# AFE_old.net
KiCad netlist of a schematic drawn in Altium Designer
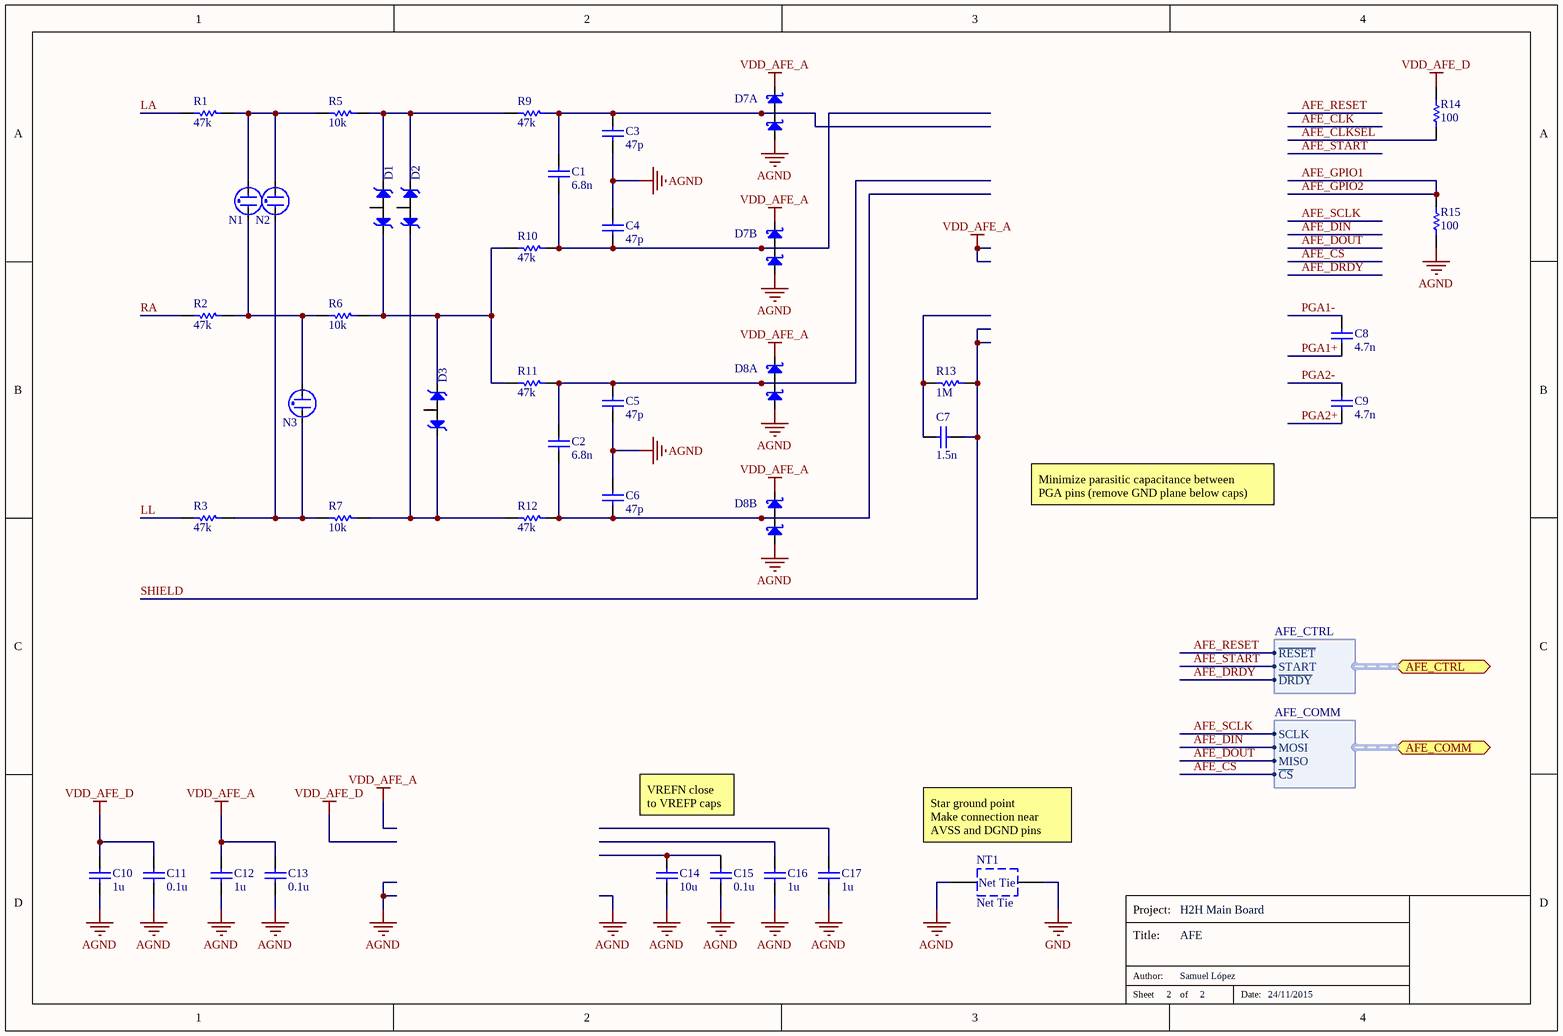
[diagram p0: AFE_old.SchDoc]

(export (version "E")
  (design (tool "Eeschema 10.0.6"))
  (components
    (comp (ref "C1")
      (value "6.8n")
      (footprint "C0603")
      (description "Capacitor")
      (libsource (lib "Common Devices") (part "Capacitor"))
    )
    (comp (ref "C2")
      (value "6.8n")
      (footprint "C0603")
      (description "Capacitor")
      (libsource (lib "Common Devices") (part "Capacitor"))
    )
    (comp (ref "C3")
      (value "47p")
      (footprint "C0603")
      (description "Capacitor")
      (libsource (lib "Common Devices") (part "Capacitor"))
    )
    (comp (ref "C4")
      (value "47p")
      (footprint "C0603")
      (description "Capacitor")
      (libsource (lib "Common Devices") (part "Capacitor"))
    )
    (comp (ref "C5")
      (value "47p")
      (footprint "C0603")
      (description "Capacitor")
      (libsource (lib "Common Devices") (part "Capacitor"))
    )
    (comp (ref "C6")
      (value "47p")
      (footprint "C0603")
      (description "Capacitor")
      (libsource (lib "Common Devices") (part "Capacitor"))
    )
    (comp (ref "C7")
      (value "1.5n")
      (footprint "C0603")
      (description "Capacitor")
      (libsource (lib "Common Devices") (part "Capacitor"))
    )
    (comp (ref "C8")
      (value "4.7n")
      (footprint "C0603")
      (description "Capacitor")
      (libsource (lib "Common Devices") (part "Capacitor"))
    )
    (comp (ref "C9")
      (value "4.7n")
      (footprint "C0603")
      (description "Capacitor")
      (libsource (lib "Common Devices") (part "Capacitor"))
    )
    (comp (ref "C10")
      (value "1u")
      (footprint "C0603")
      (description "Capacitor")
      (libsource (lib "Common Devices") (part "Capacitor"))
    )
    (comp (ref "C11")
      (value "0.1u")
      (footprint "C0603")
      (description "Capacitor")
      (libsource (lib "Common Devices") (part "Capacitor"))
    )
    (comp (ref "C12")
      (value "1u")
      (footprint "C0603")
      (description "Capacitor")
      (libsource (lib "Common Devices") (part "Capacitor"))
    )
    (comp (ref "C13")
      (value "0.1u")
      (footprint "C0603")
      (description "Capacitor")
      (libsource (lib "Common Devices") (part "Capacitor"))
    )
    (comp (ref "C14")
      (value "10u")
      (footprint "C0603")
      (description "Capacitor")
      (libsource (lib "Common Devices") (part "Capacitor"))
    )
    (comp (ref "C15")
      (value "0.1u")
      (footprint "C0603")
      (description "Capacitor")
      (libsource (lib "Common Devices") (part "Capacitor"))
    )
    (comp (ref "C16")
      (value "1u")
      (footprint "C0603")
      (description "Capacitor")
      (libsource (lib "Common Devices") (part "Capacitor"))
    )
    (comp (ref "C17")
      (value "1u")
      (footprint "C0603")
      (description "Capacitor")
      (libsource (lib "Common Devices") (part "Capacitor"))
    )
    (comp (ref "D1")
      (value "PESD5V0X1BT")
      (footprint "SOT23-3")
      (description "TVS Diode - Bidirectional")
      (libsource (lib "Main Board") (part "PESD5V0X1"))
    )
    (comp (ref "D2")
      (value "PESD5V0X1BT")
      (footprint "SOT23-3")
      (description "TVS Diode - Bidirectional")
      (libsource (lib "Main Board") (part "PESD5V0X1"))
    )
    (comp (ref "D3")
      (value "PESD5V0X1BT")
      (footprint "SOT23-3")
      (description "TVS Diode - Bidirectional")
      (libsource (lib "Main Board") (part "PESD5V0X1"))
    )
    (comp (ref "D7")
      (value "BAS70DW-04")
      (footprint "SOT-363")
      (description "Schottky Diode - Array")
      (libsource (lib "Main Board") (part "BAS70DW-04"))
    )
    (comp (ref "D8")
      (value "BAS70DW-04")
      (footprint "SOT-363")
      (description "Schottky Diode - Array")
      (libsource (lib "Main Board") (part "BAS70DW-04"))
    )
    (comp (ref "N1")
      (value "GDT")
      (footprint "1812 GDT")
      (description "GDT - Gas Discharge Tube")
      (libsource (lib "Main Board") (part "2051-09-SM"))
    )
    (comp (ref "N2")
      (value "GDT")
      (footprint "1812 GDT")
      (description "GDT - Gas Discharge Tube")
      (libsource (lib "Main Board") (part "2051-09-SM"))
    )
    (comp (ref "N3")
      (value "GDT")
      (footprint "1812 GDT")
      (description "GDT - Gas Discharge Tube")
      (libsource (lib "Main Board") (part "2051-09-SM"))
    )
    (comp (ref "NT1")
      (value "Net Tie")
      (footprint "Net Tie (AGND-DGND)")
      (description "Net Tie (AGND-DGND)")
      (libsource (lib "Common Devices") (part "Net Tie"))
    )
    (comp (ref "R1")
      (value "47k")
      (footprint "R0603")
      (description "Resistor")
      (libsource (lib "Common Devices") (part "Resistor"))
    )
    (comp (ref "R2")
      (value "47k")
      (footprint "R0603")
      (description "Resistor")
      (libsource (lib "Common Devices") (part "Resistor"))
    )
    (comp (ref "R3")
      (value "47k")
      (footprint "R0603")
      (description "Resistor")
      (libsource (lib "Common Devices") (part "Resistor"))
    )
    (comp (ref "R5")
      (value "10k")
      (footprint "R0603")
      (description "Resistor")
      (libsource (lib "Common Devices") (part "Resistor"))
    )
    (comp (ref "R6")
      (value "10k")
      (footprint "R0603")
      (description "Resistor")
      (libsource (lib "Common Devices") (part "Resistor"))
    )
    (comp (ref "R7")
      (value "10k")
      (footprint "R0603")
      (description "Resistor")
      (libsource (lib "Common Devices") (part "Resistor"))
    )
    (comp (ref "R9")
      (value "47k")
      (footprint "R0603")
      (description "Resistor")
      (libsource (lib "Common Devices") (part "Resistor"))
    )
    (comp (ref "R10")
      (value "47k")
      (footprint "R0603")
      (description "Resistor")
      (libsource (lib "Common Devices") (part "Resistor"))
    )
    (comp (ref "R11")
      (value "47k")
      (footprint "R0603")
      (description "Resistor")
      (libsource (lib "Common Devices") (part "Resistor"))
    )
    (comp (ref "R12")
      (value "47k")
      (footprint "R0603")
      (description "Resistor")
      (libsource (lib "Common Devices") (part "Resistor"))
    )
    (comp (ref "R13")
      (value "1M")
      (footprint "R0603")
      (description "Resistor")
      (libsource (lib "Common Devices") (part "Resistor"))
    )
    (comp (ref "R14")
      (value "100")
      (footprint "R0603")
      (description "Resistor")
      (libsource (lib "Common Devices") (part "Resistor"))
    )
    (comp (ref "R15")
      (value "100")
      (footprint "R0603")
      (description "Resistor")
      (libsource (lib "Common Devices") (part "Resistor"))
    )
  )
  (nets
    (net (code "4") (name "/AFE_CLKSEL") (class "Default")
      (node (ref "R14") (pin "1") (pinfunction "1_1") (pintype "passive"))
    )
    (net (code "9") (name "/AFE_GPIO1") (class "Default")
      (node (ref "R15") (pin "2") (pinfunction "2_2") (pintype "passive"))
    )
    (net (code "13") (name "/LA") (class "Default")
      (node (ref "R1") (pin "1") (pinfunction "1_1") (pintype "passive"))
    )
    (net (code "14") (name "/LL") (class "Default")
      (node (ref "R3") (pin "1") (pinfunction "1_1") (pintype "passive"))
    )
    (net (code "15") (name "/PGA1+") (class "Default")
      (node (ref "C8") (pin "1") (pinfunction "1_1") (pintype "passive"))
    )
    (net (code "16") (name "/PGA1-") (class "Default")
      (node (ref "C8") (pin "2") (pinfunction "2_2") (pintype "passive"))
    )
    (net (code "17") (name "/PGA2+") (class "Default")
      (node (ref "C9") (pin "1") (pinfunction "1_1") (pintype "passive"))
    )
    (net (code "18") (name "/PGA2-") (class "Default")
      (node (ref "C9") (pin "2") (pinfunction "2_2") (pintype "passive"))
    )
    (net (code "19") (name "/RA") (class "Default")
      (node (ref "R2") (pin "1") (pinfunction "1_1") (pintype "passive"))
    )
    (net (code "20") (name "/SHIELD") (class "Default")
      (node (ref "C7") (pin "2") (pinfunction "2_2") (pintype "passive"))
      (node (ref "R13") (pin "2") (pinfunction "2_2") (pintype "passive"))
    )
    (net (code "23") (name "AGND") (class "Default")
      (node (ref "C10") (pin "1") (pinfunction "1_1") (pintype "passive"))
      (node (ref "C11") (pin "1") (pinfunction "1_1") (pintype "passive"))
      (node (ref "C12") (pin "1") (pinfunction "1_1") (pintype "passive"))
      (node (ref "C13") (pin "1") (pinfunction "1_1") (pintype "passive"))
      (node (ref "C14") (pin "1") (pinfunction "1_1") (pintype "passive"))
      (node (ref "C15") (pin "1") (pinfunction "1_1") (pintype "passive"))
      (node (ref "C16") (pin "1") (pinfunction "1_1") (pintype "passive"))
      (node (ref "C17") (pin "1") (pinfunction "1_1") (pintype "passive"))
      (node (ref "C3") (pin "2") (pinfunction "2_2") (pintype "passive"))
      (node (ref "C4") (pin "1") (pinfunction "1_1") (pintype "passive"))
      (node (ref "C5") (pin "2") (pinfunction "2_2") (pintype "passive"))
      (node (ref "C6") (pin "1") (pinfunction "1_1") (pintype "passive"))
      (node (ref "D7") (pin "1") (pinfunction "A1_1") (pintype "passive"))
      (node (ref "D7") (pin "4") (pinfunction "A2_4") (pintype "passive"))
      (node (ref "D8") (pin "1") (pinfunction "A1_1") (pintype "passive"))
      (node (ref "D8") (pin "4") (pinfunction "A2_4") (pintype "passive"))
      (node (ref "NT1") (pin "1") (pinfunction "1_1") (pintype "passive"))
      (node (ref "R15") (pin "1") (pinfunction "1_1") (pintype "passive"))
    )
    (net (code "24") (name "GND") (class "Default")
      (node (ref "NT1") (pin "2") (pinfunction "2_2") (pintype "passive"))
    )
    (net (code "25") (name "Net-(C7-Pad1)") (class "Default")
      (node (ref "C7") (pin "1") (pinfunction "1_1") (pintype "passive"))
      (node (ref "R13") (pin "1") (pinfunction "1_1") (pintype "passive"))
    )
    (net (code "26") (name "Net-(C14-Pad2)") (class "Default")
      (node (ref "C14") (pin "2") (pinfunction "2_2") (pintype "passive"))
      (node (ref "C15") (pin "2") (pinfunction "2_2") (pintype "passive"))
    )
    (net (code "27") (name "Net-(D1-K1)") (class "Default")
      (node (ref "D1") (pin "1") (pinfunction "K1_1") (pintype "passive"))
      (node (ref "D3") (pin "2") (pinfunction "K2_2") (pintype "passive"))
      (node (ref "R10") (pin "1") (pinfunction "1_1") (pintype "passive"))
      (node (ref "R11") (pin "1") (pinfunction "1_1") (pintype "passive"))
      (node (ref "R6") (pin "2") (pinfunction "2_2") (pintype "passive"))
    )
    (net (code "28") (name "Net-(D1-K2)") (class "Default")
      (node (ref "D1") (pin "2") (pinfunction "K2_2") (pintype "passive"))
      (node (ref "D2") (pin "2") (pinfunction "K2_2") (pintype "passive"))
      (node (ref "R5") (pin "2") (pinfunction "2_2") (pintype "passive"))
      (node (ref "R9") (pin "1") (pinfunction "1_1") (pintype "passive"))
    )
    (net (code "29") (name "Net-(D2-K1)") (class "Default")
      (node (ref "D2") (pin "1") (pinfunction "K1_1") (pintype "passive"))
      (node (ref "D3") (pin "1") (pinfunction "K1_1") (pintype "passive"))
      (node (ref "R12") (pin "1") (pinfunction "1_1") (pintype "passive"))
      (node (ref "R7") (pin "2") (pinfunction "2_2") (pintype "passive"))
    )
    (net (code "30") (name "Net-(D7A-AK1)") (class "Default")
      (node (ref "C1") (pin "1") (pinfunction "1_1") (pintype "passive"))
      (node (ref "C3") (pin "1") (pinfunction "1_1") (pintype "passive"))
      (node (ref "D7") (pin "6") (pinfunction "AK1_6") (pintype "passive"))
      (node (ref "R9") (pin "2") (pinfunction "2_2") (pintype "passive"))
    )
    (net (code "31") (name "Net-(D7B-AK2)") (class "Default")
      (node (ref "C1") (pin "2") (pinfunction "2_2") (pintype "passive"))
      (node (ref "C4") (pin "2") (pinfunction "2_2") (pintype "passive"))
      (node (ref "D7") (pin "3") (pinfunction "AK2_3") (pintype "passive"))
      (node (ref "R10") (pin "2") (pinfunction "2_2") (pintype "passive"))
    )
    (net (code "32") (name "Net-(D8A-AK1)") (class "Default")
      (node (ref "C2") (pin "1") (pinfunction "1_1") (pintype "passive"))
      (node (ref "C5") (pin "1") (pinfunction "1_1") (pintype "passive"))
      (node (ref "D8") (pin "6") (pinfunction "AK1_6") (pintype "passive"))
      (node (ref "R11") (pin "2") (pinfunction "2_2") (pintype "passive"))
    )
    (net (code "33") (name "Net-(D8B-AK2)") (class "Default")
      (node (ref "C2") (pin "2") (pinfunction "2_2") (pintype "passive"))
      (node (ref "C6") (pin "2") (pinfunction "2_2") (pintype "passive"))
      (node (ref "D8") (pin "3") (pinfunction "AK2_3") (pintype "passive"))
      (node (ref "R12") (pin "2") (pinfunction "2_2") (pintype "passive"))
    )
    (net (code "34") (name "Net-(N1-Pad1)") (class "Default")
      (node (ref "N1") (pin "1") (pinfunction "1_1") (pintype "passive"))
      (node (ref "N3") (pin "2") (pinfunction "2_2") (pintype "passive"))
      (node (ref "R2") (pin "2") (pinfunction "2_2") (pintype "passive"))
      (node (ref "R6") (pin "1") (pinfunction "1_1") (pintype "passive"))
    )
    (net (code "35") (name "Net-(N1-Pad2)") (class "Default")
      (node (ref "N1") (pin "2") (pinfunction "2_2") (pintype "passive"))
      (node (ref "N2") (pin "2") (pinfunction "2_2") (pintype "passive"))
      (node (ref "R1") (pin "2") (pinfunction "2_2") (pintype "passive"))
      (node (ref "R5") (pin "1") (pinfunction "1_1") (pintype "passive"))
    )
    (net (code "36") (name "Net-(N2-Pad1)") (class "Default")
      (node (ref "N2") (pin "1") (pinfunction "1_1") (pintype "passive"))
      (node (ref "N3") (pin "1") (pinfunction "1_1") (pintype "passive"))
      (node (ref "R3") (pin "2") (pinfunction "2_2") (pintype "passive"))
      (node (ref "R7") (pin "1") (pinfunction "1_1") (pintype "passive"))
    )
    (net (code "37") (name "VDD_AFE_A") (class "Default")
      (node (ref "C12") (pin "2") (pinfunction "2_2") (pintype "passive"))
      (node (ref "C13") (pin "2") (pinfunction "2_2") (pintype "passive"))
      (node (ref "D7") (pin "2") (pinfunction "K1_2") (pintype "passive"))
      (node (ref "D7") (pin "5") (pinfunction "K2_5") (pintype "passive"))
      (node (ref "D8") (pin "2") (pinfunction "K1_2") (pintype "passive"))
      (node (ref "D8") (pin "5") (pinfunction "K2_5") (pintype "passive"))
    )
    (net (code "38") (name "VDD_AFE_D") (class "Default")
      (node (ref "C10") (pin "2") (pinfunction "2_2") (pintype "passive"))
      (node (ref "C11") (pin "2") (pinfunction "2_2") (pintype "passive"))
      (node (ref "R14") (pin "2") (pinfunction "2_2") (pintype "passive"))
    )
    (net (code "39") (name "unconnected-(C16-Pad2)") (class "Default")
      (node (ref "C16") (pin "2") (pinfunction "2_2") (pintype "passive"))
    )
    (net (code "40") (name "unconnected-(C17-Pad2)") (class "Default")
      (node (ref "C17") (pin "2") (pinfunction "2_2") (pintype "passive"))
    )
    (net (code "41") (name "unconnected-(D1-A-Pad3)") (class "Default")
      (node (ref "D1") (pin "3") (pinfunction "A_3") (pintype "passive"))
    )
    (net (code "42") (name "unconnected-(D2-A-Pad3)") (class "Default")
      (node (ref "D2") (pin "3") (pinfunction "A_3") (pintype "passive"))
    )
    (net (code "43") (name "unconnected-(D3-A-Pad3)") (class "Default")
      (node (ref "D3") (pin "3") (pinfunction "A_3") (pintype "passive"))
    )
  )
)
